# CON_NB3000_ATE_INTF.net
KiCad netlist of a schematic drawn in Altium Designer
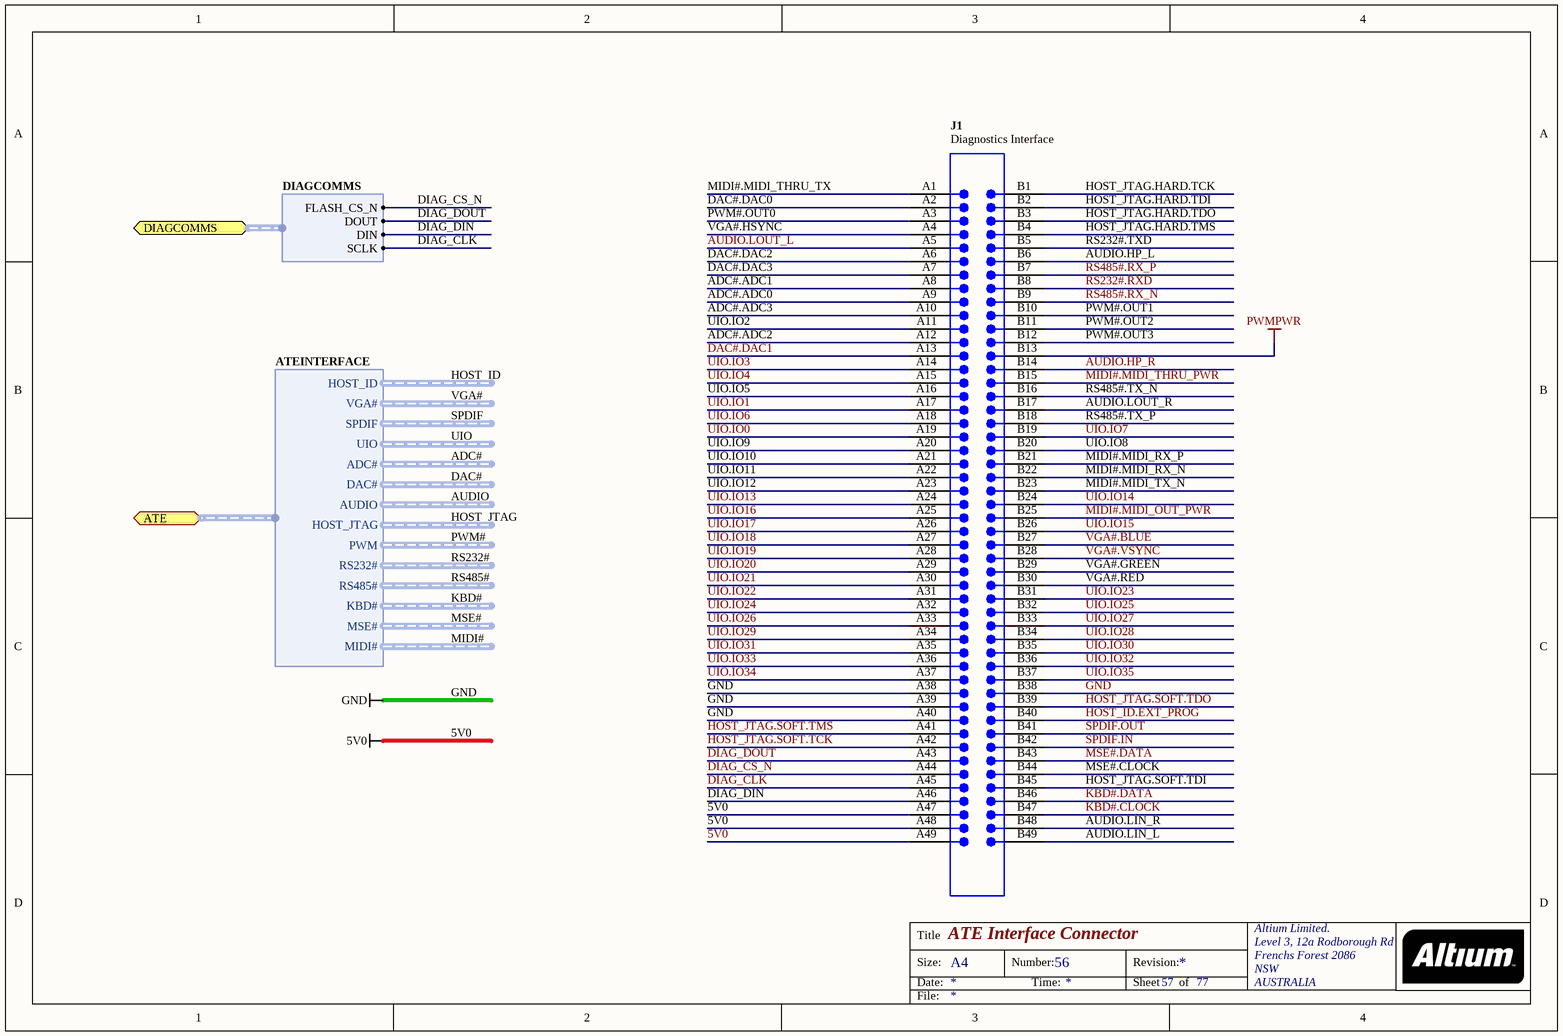
[diagram p0: CON_NB3000_ATE_INTF.SchDoc]

(export (version "E")
  (design (tool "Eeschema 10.0.6"))
  (components
    (comp (ref "J1")
      (value "Diagnostics Interface")
      (footprint "EDGE-PCIE-X8")
      (description "Connector, PCI Express, Used for Automatic Test Equipment (ATE)")
      (libsource (lib "AltiumDesignLibrary") (part "CON-PCIE-EDGE"))
    )
  )
  (nets
    (net (code "17") (name "/ADC#.ADC0") (class "Default")
      (node (ref "J1") (pin "A9") (pinfunction "A9_A9") (pintype "passive"))
    )
    (net (code "18") (name "/ADC#.ADC1") (class "Default")
      (node (ref "J1") (pin "A8") (pinfunction "A8_A8") (pintype "passive"))
    )
    (net (code "19") (name "/ADC#.ADC2") (class "Default")
      (node (ref "J1") (pin "A12") (pinfunction "A12_A12") (pintype "passive"))
    )
    (net (code "20") (name "/ADC#.ADC3") (class "Default")
      (node (ref "J1") (pin "A10") (pinfunction "A10_A10") (pintype "passive"))
    )
    (net (code "22") (name "/AUDIO.HP_L") (class "Default")
      (node (ref "J1") (pin "B6") (pinfunction "B6_B6") (pintype "passive"))
    )
    (net (code "23") (name "/AUDIO.HP_R") (class "Default")
      (node (ref "J1") (pin "B14") (pinfunction "B14_B14") (pintype "passive"))
    )
    (net (code "24") (name "/AUDIO.LIN_L") (class "Default")
      (node (ref "J1") (pin "B49") (pinfunction "B49_B49") (pintype "passive"))
    )
    (net (code "25") (name "/AUDIO.LIN_R") (class "Default")
      (node (ref "J1") (pin "B48") (pinfunction "B48_B48") (pintype "passive"))
    )
    (net (code "26") (name "/AUDIO.LOUT_L") (class "Default")
      (node (ref "J1") (pin "A5") (pinfunction "A5_A5") (pintype "passive"))
    )
    (net (code "27") (name "/AUDIO.LOUT_R") (class "Default")
      (node (ref "J1") (pin "B17") (pinfunction "B17_B17") (pintype "passive"))
    )
    (net (code "28") (name "/DAC#.DAC0") (class "Default")
      (node (ref "J1") (pin "A2") (pinfunction "A2_A2") (pintype "passive"))
    )
    (net (code "29") (name "/DAC#.DAC1") (class "Default")
      (node (ref "J1") (pin "A13") (pinfunction "A13_A13") (pintype "passive"))
    )
    (net (code "30") (name "/DAC#.DAC2") (class "Default")
      (node (ref "J1") (pin "A6") (pinfunction "A6_A6") (pintype "passive"))
    )
    (net (code "31") (name "/DAC#.DAC3") (class "Default")
      (node (ref "J1") (pin "A7") (pinfunction "A7_A7") (pintype "passive"))
    )
    (net (code "32") (name "/DIAG_CLK") (class "Default")
      (node (ref "J1") (pin "A45") (pinfunction "A45_A45") (pintype "passive"))
    )
    (net (code "33") (name "/DIAG_CS_N") (class "Default")
      (node (ref "J1") (pin "A44") (pinfunction "A44_A44") (pintype "passive"))
    )
    (net (code "34") (name "/DIAG_DIN") (class "Default")
      (node (ref "J1") (pin "A46") (pinfunction "A46_A46") (pintype "passive"))
    )
    (net (code "35") (name "/DIAG_DOUT") (class "Default")
      (node (ref "J1") (pin "A43") (pinfunction "A43_A43") (pintype "passive"))
    )
    (net (code "36") (name "/HOST_ID.EXT_PROG") (class "Default")
      (node (ref "J1") (pin "B40") (pinfunction "B40_B40") (pintype "passive"))
    )
    (net (code "37") (name "/HOST_JTAG.HARD.TCK") (class "Default")
      (node (ref "J1") (pin "B1") (pinfunction "B1_B1") (pintype "passive"))
    )
    (net (code "38") (name "/HOST_JTAG.HARD.TDI") (class "Default")
      (node (ref "J1") (pin "B2") (pinfunction "B2_B2") (pintype "passive"))
    )
    (net (code "39") (name "/HOST_JTAG.HARD.TDO") (class "Default")
      (node (ref "J1") (pin "B3") (pinfunction "B3_B3") (pintype "passive"))
    )
    (net (code "40") (name "/HOST_JTAG.HARD.TMS") (class "Default")
      (node (ref "J1") (pin "B4") (pinfunction "B4_B4") (pintype "passive"))
    )
    (net (code "41") (name "/HOST_JTAG.SOFT.TCK") (class "Default")
      (node (ref "J1") (pin "A42") (pinfunction "A42_A42") (pintype "passive"))
    )
    (net (code "42") (name "/HOST_JTAG.SOFT.TDI") (class "Default")
      (node (ref "J1") (pin "B45") (pinfunction "B45_B45") (pintype "passive"))
    )
    (net (code "43") (name "/HOST_JTAG.SOFT.TDO") (class "Default")
      (node (ref "J1") (pin "B39") (pinfunction "B39_B39") (pintype "passive"))
    )
    (net (code "44") (name "/HOST_JTAG.SOFT.TMS") (class "Default")
      (node (ref "J1") (pin "A41") (pinfunction "A41_A41") (pintype "passive"))
    )
    (net (code "45") (name "/KBD#.CLOCK") (class "Default")
      (node (ref "J1") (pin "B47") (pinfunction "B47_B47") (pintype "passive"))
    )
    (net (code "46") (name "/KBD#.DATA") (class "Default")
      (node (ref "J1") (pin "B46") (pinfunction "B46_B46") (pintype "passive"))
    )
    (net (code "47") (name "/MIDI#.MIDI_OUT_PWR") (class "Default")
      (node (ref "J1") (pin "B25") (pinfunction "B25_B25") (pintype "passive"))
    )
    (net (code "48") (name "/MIDI#.MIDI_RX_N") (class "Default")
      (node (ref "J1") (pin "B22") (pinfunction "B22_B22") (pintype "passive"))
    )
    (net (code "49") (name "/MIDI#.MIDI_RX_P") (class "Default")
      (node (ref "J1") (pin "B21") (pinfunction "B21_B21") (pintype "passive"))
    )
    (net (code "50") (name "/MIDI#.MIDI_THRU_PWR") (class "Default")
      (node (ref "J1") (pin "B15") (pinfunction "B15_B15") (pintype "passive"))
    )
    (net (code "51") (name "/MIDI#.MIDI_THRU_TX") (class "Default")
      (node (ref "J1") (pin "A1") (pinfunction "A1_A1") (pintype "passive"))
    )
    (net (code "52") (name "/MIDI#.MIDI_TX_N") (class "Default")
      (node (ref "J1") (pin "B23") (pinfunction "B23_B23") (pintype "passive"))
    )
    (net (code "53") (name "/MSE#.CLOCK") (class "Default")
      (node (ref "J1") (pin "B44") (pinfunction "B44_B44") (pintype "passive"))
    )
    (net (code "54") (name "/MSE#.DATA") (class "Default")
      (node (ref "J1") (pin "B43") (pinfunction "B43_B43") (pintype "passive"))
    )
    (net (code "56") (name "/PWM#.OUT0") (class "Default")
      (node (ref "J1") (pin "A3") (pinfunction "A3_A3") (pintype "passive"))
    )
    (net (code "57") (name "/PWM#.OUT1") (class "Default")
      (node (ref "J1") (pin "B10") (pinfunction "B10_B10") (pintype "passive"))
    )
    (net (code "58") (name "/PWM#.OUT2") (class "Default")
      (node (ref "J1") (pin "B11") (pinfunction "B11_B11") (pintype "passive"))
    )
    (net (code "59") (name "/PWM#.OUT3") (class "Default")
      (node (ref "J1") (pin "B12") (pinfunction "B12_B12") (pintype "passive"))
    )
    (net (code "60") (name "/RS232#.RXD") (class "Default")
      (node (ref "J1") (pin "B8") (pinfunction "B8_B8") (pintype "passive"))
    )
    (net (code "61") (name "/RS232#.TXD") (class "Default")
      (node (ref "J1") (pin "B5") (pinfunction "B5_B5") (pintype "passive"))
    )
    (net (code "62") (name "/RS485#.RX_N") (class "Default")
      (node (ref "J1") (pin "B9") (pinfunction "B9_B9") (pintype "passive"))
    )
    (net (code "63") (name "/RS485#.RX_P") (class "Default")
      (node (ref "J1") (pin "B7") (pinfunction "B7_B7") (pintype "passive"))
    )
    (net (code "64") (name "/RS485#.TX_N") (class "Default")
      (node (ref "J1") (pin "B16") (pinfunction "B16_B16") (pintype "passive"))
    )
    (net (code "65") (name "/RS485#.TX_P") (class "Default")
      (node (ref "J1") (pin "B18") (pinfunction "B18_B18") (pintype "passive"))
    )
    (net (code "66") (name "/SPDIF.IN") (class "Default")
      (node (ref "J1") (pin "B42") (pinfunction "B42_B42") (pintype "passive"))
    )
    (net (code "67") (name "/SPDIF.OUT") (class "Default")
      (node (ref "J1") (pin "B41") (pinfunction "B41_B41") (pintype "passive"))
    )
    (net (code "68") (name "/UIO.IO0") (class "Default")
      (node (ref "J1") (pin "A19") (pinfunction "A19_A19") (pintype "passive"))
    )
    (net (code "69") (name "/UIO.IO1") (class "Default")
      (node (ref "J1") (pin "A17") (pinfunction "A17_A17") (pintype "passive"))
    )
    (net (code "70") (name "/UIO.IO2") (class "Default")
      (node (ref "J1") (pin "A11") (pinfunction "A11_A11") (pintype "passive"))
    )
    (net (code "71") (name "/UIO.IO3") (class "Default")
      (node (ref "J1") (pin "A14") (pinfunction "A14_A14") (pintype "passive"))
    )
    (net (code "72") (name "/UIO.IO4") (class "Default")
      (node (ref "J1") (pin "A15") (pinfunction "A15_A15") (pintype "passive"))
    )
    (net (code "73") (name "/UIO.IO5") (class "Default")
      (node (ref "J1") (pin "A16") (pinfunction "A16_A16") (pintype "passive"))
    )
    (net (code "74") (name "/UIO.IO6") (class "Default")
      (node (ref "J1") (pin "A18") (pinfunction "A18_A18") (pintype "passive"))
    )
    (net (code "75") (name "/UIO.IO7") (class "Default")
      (node (ref "J1") (pin "B19") (pinfunction "B19_B19") (pintype "passive"))
    )
    (net (code "76") (name "/UIO.IO8") (class "Default")
      (node (ref "J1") (pin "B20") (pinfunction "B20_B20") (pintype "passive"))
    )
    (net (code "77") (name "/UIO.IO9") (class "Default")
      (node (ref "J1") (pin "A20") (pinfunction "A20_A20") (pintype "passive"))
    )
    (net (code "78") (name "/UIO.IO10") (class "Default")
      (node (ref "J1") (pin "A21") (pinfunction "A21_A21") (pintype "passive"))
    )
    (net (code "79") (name "/UIO.IO11") (class "Default")
      (node (ref "J1") (pin "A22") (pinfunction "A22_A22") (pintype "passive"))
    )
    (net (code "80") (name "/UIO.IO12") (class "Default")
      (node (ref "J1") (pin "A23") (pinfunction "A23_A23") (pintype "passive"))
    )
    (net (code "81") (name "/UIO.IO13") (class "Default")
      (node (ref "J1") (pin "A24") (pinfunction "A24_A24") (pintype "passive"))
    )
    (net (code "82") (name "/UIO.IO14") (class "Default")
      (node (ref "J1") (pin "B24") (pinfunction "B24_B24") (pintype "passive"))
    )
    (net (code "83") (name "/UIO.IO15") (class "Default")
      (node (ref "J1") (pin "B26") (pinfunction "B26_B26") (pintype "passive"))
    )
    (net (code "84") (name "/UIO.IO16") (class "Default")
      (node (ref "J1") (pin "A25") (pinfunction "A25_A25") (pintype "passive"))
    )
    (net (code "85") (name "/UIO.IO17") (class "Default")
      (node (ref "J1") (pin "A26") (pinfunction "A26_A26") (pintype "passive"))
    )
    (net (code "86") (name "/UIO.IO18") (class "Default")
      (node (ref "J1") (pin "A27") (pinfunction "A27_A27") (pintype "passive"))
    )
    (net (code "87") (name "/UIO.IO19") (class "Default")
      (node (ref "J1") (pin "A28") (pinfunction "A28_A28") (pintype "passive"))
    )
    (net (code "88") (name "/UIO.IO20") (class "Default")
      (node (ref "J1") (pin "A29") (pinfunction "A29_A29") (pintype "passive"))
    )
    (net (code "89") (name "/UIO.IO21") (class "Default")
      (node (ref "J1") (pin "A30") (pinfunction "A30_A30") (pintype "passive"))
    )
    (net (code "90") (name "/UIO.IO22") (class "Default")
      (node (ref "J1") (pin "A31") (pinfunction "A31_A31") (pintype "passive"))
    )
    (net (code "91") (name "/UIO.IO23") (class "Default")
      (node (ref "J1") (pin "B31") (pinfunction "B31_B31") (pintype "passive"))
    )
    (net (code "92") (name "/UIO.IO24") (class "Default")
      (node (ref "J1") (pin "A32") (pinfunction "A32_A32") (pintype "passive"))
    )
    (net (code "93") (name "/UIO.IO25") (class "Default")
      (node (ref "J1") (pin "B32") (pinfunction "B32_B32") (pintype "passive"))
    )
    (net (code "94") (name "/UIO.IO26") (class "Default")
      (node (ref "J1") (pin "A33") (pinfunction "A33_A33") (pintype "passive"))
    )
    (net (code "95") (name "/UIO.IO27") (class "Default")
      (node (ref "J1") (pin "B33") (pinfunction "B33_B33") (pintype "passive"))
    )
    (net (code "96") (name "/UIO.IO28") (class "Default")
      (node (ref "J1") (pin "B34") (pinfunction "B34_B34") (pintype "passive"))
    )
    (net (code "97") (name "/UIO.IO29") (class "Default")
      (node (ref "J1") (pin "A34") (pinfunction "A34_A34") (pintype "passive"))
    )
    (net (code "98") (name "/UIO.IO30") (class "Default")
      (node (ref "J1") (pin "B35") (pinfunction "B35_B35") (pintype "passive"))
    )
    (net (code "99") (name "/UIO.IO31") (class "Default")
      (node (ref "J1") (pin "A35") (pinfunction "A35_A35") (pintype "passive"))
    )
    (net (code "100") (name "/UIO.IO32") (class "Default")
      (node (ref "J1") (pin "B36") (pinfunction "B36_B36") (pintype "passive"))
    )
    (net (code "101") (name "/UIO.IO33") (class "Default")
      (node (ref "J1") (pin "A36") (pinfunction "A36_A36") (pintype "passive"))
    )
    (net (code "102") (name "/UIO.IO34") (class "Default")
      (node (ref "J1") (pin "A37") (pinfunction "A37_A37") (pintype "passive"))
    )
    (net (code "103") (name "/UIO.IO35") (class "Default")
      (node (ref "J1") (pin "B37") (pinfunction "B37_B37") (pintype "passive"))
    )
    (net (code "104") (name "/VGA#.BLUE") (class "Default")
      (node (ref "J1") (pin "B27") (pinfunction "B27_B27") (pintype "passive"))
    )
    (net (code "105") (name "/VGA#.GREEN") (class "Default")
      (node (ref "J1") (pin "B29") (pinfunction "B29_B29") (pintype "passive"))
    )
    (net (code "106") (name "/VGA#.HSYNC") (class "Default")
      (node (ref "J1") (pin "A4") (pinfunction "A4_A4") (pintype "passive"))
    )
    (net (code "107") (name "/VGA#.RED") (class "Default")
      (node (ref "J1") (pin "B30") (pinfunction "B30_B30") (pintype "passive"))
    )
    (net (code "108") (name "/VGA#.VSYNC") (class "Default")
      (node (ref "J1") (pin "B28") (pinfunction "B28_B28") (pintype "passive"))
    )
    (net (code "123") (name "5V0") (class "Default")
      (node (ref "J1") (pin "A47") (pinfunction "A47_A47") (pintype "passive"))
      (node (ref "J1") (pin "A48") (pinfunction "A48_A48") (pintype "passive"))
      (node (ref "J1") (pin "A49") (pinfunction "A49_A49") (pintype "passive"))
    )
    (net (code "124") (name "GND") (class "Default")
      (node (ref "J1") (pin "A38") (pinfunction "A38_A38") (pintype "passive"))
      (node (ref "J1") (pin "A39") (pinfunction "A39_A39") (pintype "passive"))
      (node (ref "J1") (pin "A40") (pinfunction "A40_A40") (pintype "passive"))
      (node (ref "J1") (pin "B38") (pinfunction "B38_B38") (pintype "passive"))
    )
    (net (code "125") (name "PWMPWR") (class "Default")
      (node (ref "J1") (pin "B13") (pinfunction "B13_B13") (pintype "passive"))
    )
  )
)
